# NeoPixel_6x4_Matrix.net
KiCad netlist of a schematic drawn in EAGLE
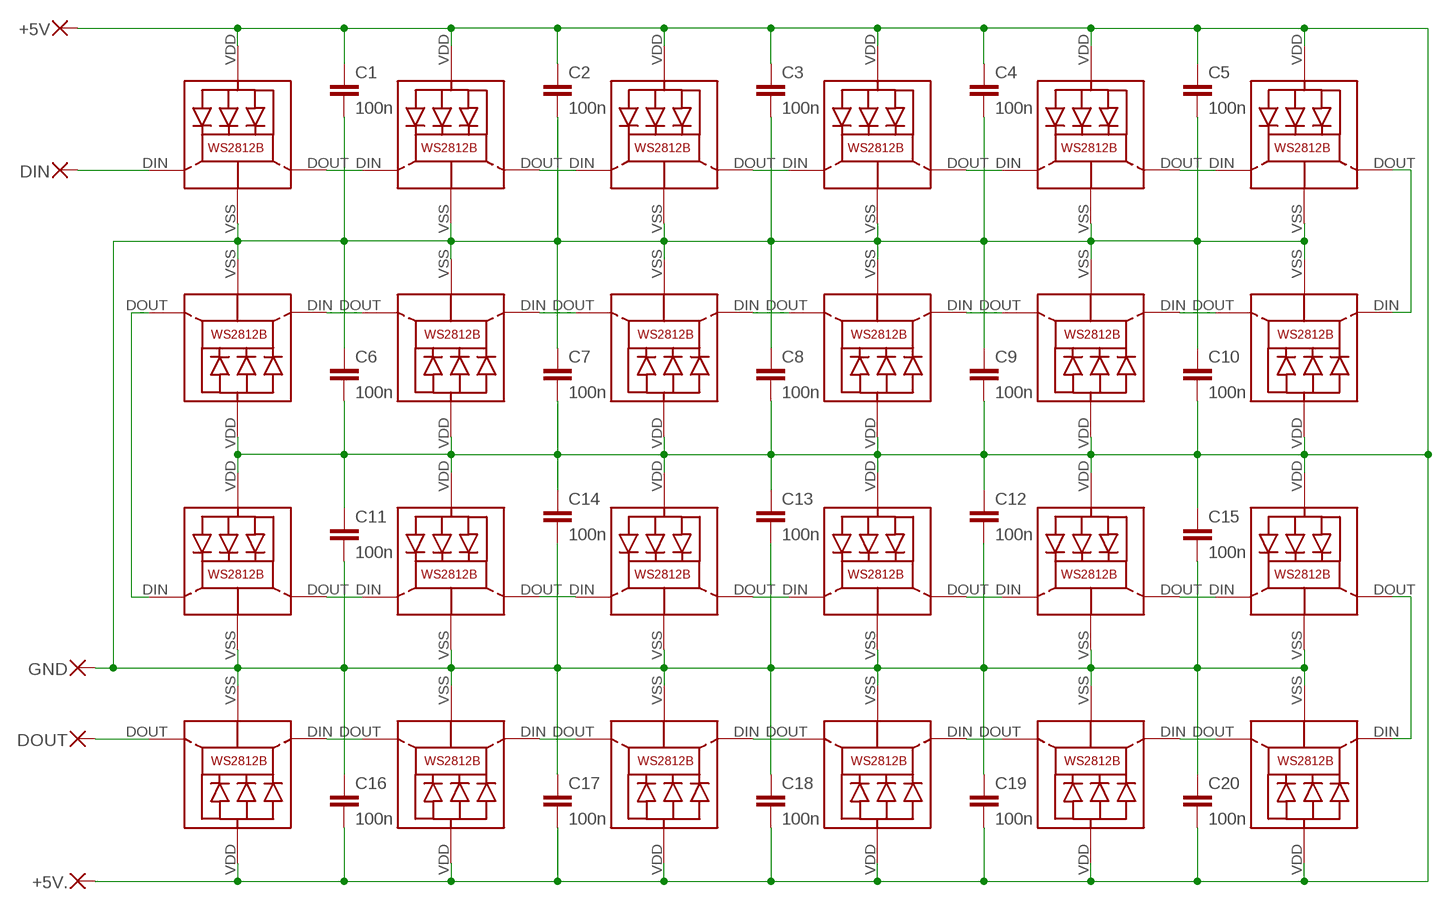
[diagram p0: schematic, sheet 1]

(export (version "E")
  (design (tool "Eeschema 10.0.6"))
  (components
    (comp (ref "+5V")
      (value "1,6/0,8")
      (footprint "eagle-import:1,6_0,8")
      (libsource (lib "eagle-import") (part "1,6/0,8"))
    )
    (comp (ref "+5V.")
      (value "1,6/0,8")
      (footprint "eagle-import:1,6_0,8")
      (libsource (lib "eagle-import") (part "1,6/0,8"))
    )
    (comp (ref "C1")
      (value "100n")
      (footprint "eagle-import:C0603")
      (libsource (lib "eagle-import") (part "C-EUC0603"))
    )
    (comp (ref "C2")
      (value "100n")
      (footprint "eagle-import:C0603")
      (libsource (lib "eagle-import") (part "C-EUC0603"))
    )
    (comp (ref "C3")
      (value "100n")
      (footprint "eagle-import:C0603")
      (libsource (lib "eagle-import") (part "C-EUC0603"))
    )
    (comp (ref "C4")
      (value "100n")
      (footprint "eagle-import:C0603")
      (libsource (lib "eagle-import") (part "C-EUC0603"))
    )
    (comp (ref "C5")
      (value "100n")
      (footprint "eagle-import:C0603")
      (libsource (lib "eagle-import") (part "C-EUC0603"))
    )
    (comp (ref "C6")
      (value "100n")
      (footprint "eagle-import:C0603")
      (libsource (lib "eagle-import") (part "C-EUC0603"))
    )
    (comp (ref "C7")
      (value "100n")
      (footprint "eagle-import:C0603")
      (libsource (lib "eagle-import") (part "C-EUC0603"))
    )
    (comp (ref "C8")
      (value "100n")
      (footprint "eagle-import:C0603")
      (libsource (lib "eagle-import") (part "C-EUC0603"))
    )
    (comp (ref "C9")
      (value "100n")
      (footprint "eagle-import:C0603")
      (libsource (lib "eagle-import") (part "C-EUC0603"))
    )
    (comp (ref "C10")
      (value "100n")
      (footprint "eagle-import:C0603")
      (libsource (lib "eagle-import") (part "C-EUC0603"))
    )
    (comp (ref "C11")
      (value "100n")
      (footprint "eagle-import:C0603")
      (libsource (lib "eagle-import") (part "C-EUC0603"))
    )
    (comp (ref "C12")
      (value "100n")
      (footprint "eagle-import:C0603")
      (libsource (lib "eagle-import") (part "C-EUC0603"))
    )
    (comp (ref "C13")
      (value "100n")
      (footprint "eagle-import:C0603")
      (libsource (lib "eagle-import") (part "C-EUC0603"))
    )
    (comp (ref "C14")
      (value "100n")
      (footprint "eagle-import:C0603")
      (libsource (lib "eagle-import") (part "C-EUC0603"))
    )
    (comp (ref "C15")
      (value "100n")
      (footprint "eagle-import:C0603")
      (libsource (lib "eagle-import") (part "C-EUC0603"))
    )
    (comp (ref "C16")
      (value "100n")
      (footprint "eagle-import:C0603")
      (libsource (lib "eagle-import") (part "C-EUC0603"))
    )
    (comp (ref "C17")
      (value "100n")
      (footprint "eagle-import:C0603")
      (libsource (lib "eagle-import") (part "C-EUC0603"))
    )
    (comp (ref "C18")
      (value "100n")
      (footprint "eagle-import:C0603")
      (libsource (lib "eagle-import") (part "C-EUC0603"))
    )
    (comp (ref "C19")
      (value "100n")
      (footprint "eagle-import:C0603")
      (libsource (lib "eagle-import") (part "C-EUC0603"))
    )
    (comp (ref "C20")
      (value "100n")
      (footprint "eagle-import:C0603")
      (libsource (lib "eagle-import") (part "C-EUC0603"))
    )
    (comp (ref "DIN")
      (value "1,6/0,8")
      (footprint "eagle-import:1,6_0,8")
      (libsource (lib "eagle-import") (part "1,6/0,8"))
    )
    (comp (ref "DOUT")
      (value "1,6/0,8")
      (footprint "eagle-import:1,6_0,8")
      (libsource (lib "eagle-import") (part "1,6/0,8"))
    )
    (comp (ref "GND")
      (value "1,6/0,8")
      (footprint "eagle-import:1,6_0,8")
      (libsource (lib "eagle-import") (part "1,6/0,8"))
    )
    (comp (ref "LED1")
      (value "WS2812B")
      (footprint "eagle-import:WS2812B")
      (libsource (lib "eagle-import") (part "WS2812B"))
    )
    (comp (ref "LED2")
      (value "WS2812B")
      (footprint "eagle-import:WS2812B")
      (libsource (lib "eagle-import") (part "WS2812B"))
    )
    (comp (ref "LED3")
      (value "WS2812B")
      (footprint "eagle-import:WS2812B")
      (libsource (lib "eagle-import") (part "WS2812B"))
    )
    (comp (ref "LED4")
      (value "WS2812B")
      (footprint "eagle-import:WS2812B")
      (libsource (lib "eagle-import") (part "WS2812B"))
    )
    (comp (ref "LED5")
      (value "WS2812B")
      (footprint "eagle-import:WS2812B")
      (libsource (lib "eagle-import") (part "WS2812B"))
    )
    (comp (ref "LED6")
      (value "WS2812B")
      (footprint "eagle-import:WS2812B")
      (libsource (lib "eagle-import") (part "WS2812B"))
    )
    (comp (ref "LED7")
      (value "WS2812B")
      (footprint "eagle-import:WS2812B")
      (libsource (lib "eagle-import") (part "WS2812B"))
    )
    (comp (ref "LED8")
      (value "WS2812B")
      (footprint "eagle-import:WS2812B")
      (libsource (lib "eagle-import") (part "WS2812B"))
    )
    (comp (ref "LED9")
      (value "WS2812B")
      (footprint "eagle-import:WS2812B")
      (libsource (lib "eagle-import") (part "WS2812B"))
    )
    (comp (ref "LED10")
      (value "WS2812B")
      (footprint "eagle-import:WS2812B")
      (libsource (lib "eagle-import") (part "WS2812B"))
    )
    (comp (ref "LED11")
      (value "WS2812B")
      (footprint "eagle-import:WS2812B")
      (libsource (lib "eagle-import") (part "WS2812B"))
    )
    (comp (ref "LED12")
      (value "WS2812B")
      (footprint "eagle-import:WS2812B")
      (libsource (lib "eagle-import") (part "WS2812B"))
    )
    (comp (ref "LED13")
      (value "WS2812B")
      (footprint "eagle-import:WS2812B")
      (libsource (lib "eagle-import") (part "WS2812B"))
    )
    (comp (ref "LED14")
      (value "WS2812B")
      (footprint "eagle-import:WS2812B")
      (libsource (lib "eagle-import") (part "WS2812B"))
    )
    (comp (ref "LED15")
      (value "WS2812B")
      (footprint "eagle-import:WS2812B")
      (libsource (lib "eagle-import") (part "WS2812B"))
    )
    (comp (ref "LED16")
      (value "WS2812B")
      (footprint "eagle-import:WS2812B")
      (libsource (lib "eagle-import") (part "WS2812B"))
    )
    (comp (ref "LED17")
      (value "WS2812B")
      (footprint "eagle-import:WS2812B")
      (libsource (lib "eagle-import") (part "WS2812B"))
    )
    (comp (ref "LED18")
      (value "WS2812B")
      (footprint "eagle-import:WS2812B")
      (libsource (lib "eagle-import") (part "WS2812B"))
    )
    (comp (ref "LED19")
      (value "WS2812B")
      (footprint "eagle-import:WS2812B")
      (libsource (lib "eagle-import") (part "WS2812B"))
    )
    (comp (ref "LED20")
      (value "WS2812B")
      (footprint "eagle-import:WS2812B")
      (libsource (lib "eagle-import") (part "WS2812B"))
    )
    (comp (ref "LED21")
      (value "WS2812B")
      (footprint "eagle-import:WS2812B")
      (libsource (lib "eagle-import") (part "WS2812B"))
    )
    (comp (ref "LED22")
      (value "WS2812B")
      (footprint "eagle-import:WS2812B")
      (libsource (lib "eagle-import") (part "WS2812B"))
    )
    (comp (ref "LED23")
      (value "WS2812B")
      (footprint "eagle-import:WS2812B")
      (libsource (lib "eagle-import") (part "WS2812B"))
    )
    (comp (ref "LED24")
      (value "WS2812B")
      (footprint "eagle-import:WS2812B")
      (libsource (lib "eagle-import") (part "WS2812B"))
    )
  )
  (nets
    (net (code "1") (name "Net-(+5V-P)") (class "Default")
      (node (ref "+5V") (pin "1") (pinfunction "P_1") (pintype "passive"))
      (node (ref "+5V.") (pin "1") (pinfunction "P_1") (pintype "passive"))
      (node (ref "C1") (pin "1") (pinfunction "1_1") (pintype "passive"))
      (node (ref "C10") (pin "2") (pinfunction "2_2") (pintype "passive"))
      (node (ref "C11") (pin "1") (pinfunction "1_1") (pintype "passive"))
      (node (ref "C12") (pin "1") (pinfunction "1_1") (pintype "passive"))
      (node (ref "C13") (pin "1") (pinfunction "1_1") (pintype "passive"))
      (node (ref "C14") (pin "1") (pinfunction "1_1") (pintype "passive"))
      (node (ref "C15") (pin "1") (pinfunction "1_1") (pintype "passive"))
      (node (ref "C16") (pin "2") (pinfunction "2_2") (pintype "passive"))
      (node (ref "C17") (pin "2") (pinfunction "2_2") (pintype "passive"))
      (node (ref "C18") (pin "2") (pinfunction "2_2") (pintype "passive"))
      (node (ref "C19") (pin "2") (pinfunction "2_2") (pintype "passive"))
      (node (ref "C2") (pin "1") (pinfunction "1_1") (pintype "passive"))
      (node (ref "C20") (pin "2") (pinfunction "2_2") (pintype "passive"))
      (node (ref "C3") (pin "1") (pinfunction "1_1") (pintype "passive"))
      (node (ref "C4") (pin "1") (pinfunction "1_1") (pintype "passive"))
      (node (ref "C5") (pin "1") (pinfunction "1_1") (pintype "passive"))
      (node (ref "C6") (pin "2") (pinfunction "2_2") (pintype "passive"))
      (node (ref "C7") (pin "2") (pinfunction "2_2") (pintype "passive"))
      (node (ref "C8") (pin "2") (pinfunction "2_2") (pintype "passive"))
      (node (ref "C9") (pin "2") (pinfunction "2_2") (pintype "passive"))
      (node (ref "LED1") (pin "VDD") (pinfunction "VDD_VDD") (pintype "power_in"))
      (node (ref "LED10") (pin "VDD") (pinfunction "VDD_VDD") (pintype "power_in"))
      (node (ref "LED11") (pin "VDD") (pinfunction "VDD_VDD") (pintype "power_in"))
      (node (ref "LED12") (pin "VDD") (pinfunction "VDD_VDD") (pintype "power_in"))
      (node (ref "LED13") (pin "VDD") (pinfunction "VDD_VDD") (pintype "power_in"))
      (node (ref "LED14") (pin "VDD") (pinfunction "VDD_VDD") (pintype "power_in"))
      (node (ref "LED15") (pin "VDD") (pinfunction "VDD_VDD") (pintype "power_in"))
      (node (ref "LED16") (pin "VDD") (pinfunction "VDD_VDD") (pintype "power_in"))
      (node (ref "LED17") (pin "VDD") (pinfunction "VDD_VDD") (pintype "power_in"))
      (node (ref "LED18") (pin "VDD") (pinfunction "VDD_VDD") (pintype "power_in"))
      (node (ref "LED19") (pin "VDD") (pinfunction "VDD_VDD") (pintype "power_in"))
      (node (ref "LED2") (pin "VDD") (pinfunction "VDD_VDD") (pintype "power_in"))
      (node (ref "LED20") (pin "VDD") (pinfunction "VDD_VDD") (pintype "power_in"))
      (node (ref "LED21") (pin "VDD") (pinfunction "VDD_VDD") (pintype "power_in"))
      (node (ref "LED22") (pin "VDD") (pinfunction "VDD_VDD") (pintype "power_in"))
      (node (ref "LED23") (pin "VDD") (pinfunction "VDD_VDD") (pintype "power_in"))
      (node (ref "LED24") (pin "VDD") (pinfunction "VDD_VDD") (pintype "power_in"))
      (node (ref "LED3") (pin "VDD") (pinfunction "VDD_VDD") (pintype "power_in"))
      (node (ref "LED4") (pin "VDD") (pinfunction "VDD_VDD") (pintype "power_in"))
      (node (ref "LED5") (pin "VDD") (pinfunction "VDD_VDD") (pintype "power_in"))
      (node (ref "LED6") (pin "VDD") (pinfunction "VDD_VDD") (pintype "power_in"))
      (node (ref "LED7") (pin "VDD") (pinfunction "VDD_VDD") (pintype "power_in"))
      (node (ref "LED8") (pin "VDD") (pinfunction "VDD_VDD") (pintype "power_in"))
      (node (ref "LED9") (pin "VDD") (pinfunction "VDD_VDD") (pintype "power_in"))
    )
    (net (code "2") (name "Net-(DIN-P)") (class "Default")
      (node (ref "DIN") (pin "1") (pinfunction "P_1") (pintype "passive"))
      (node (ref "LED1") (pin "DIN") (pinfunction "DI_DIN") (pintype "input"))
    )
    (net (code "3") (name "Net-(DOUT-P)") (class "Default")
      (node (ref "DOUT") (pin "1") (pinfunction "P_1") (pintype "passive"))
      (node (ref "LED24") (pin "DOUT") (pinfunction "DO_DOUT") (pintype "output"))
    )
    (net (code "4") (name "Net-(GND-P)") (class "Default")
      (node (ref "C1") (pin "2") (pinfunction "2_2") (pintype "passive"))
      (node (ref "C10") (pin "1") (pinfunction "1_1") (pintype "passive"))
      (node (ref "C11") (pin "2") (pinfunction "2_2") (pintype "passive"))
      (node (ref "C12") (pin "2") (pinfunction "2_2") (pintype "passive"))
      (node (ref "C13") (pin "2") (pinfunction "2_2") (pintype "passive"))
      (node (ref "C14") (pin "2") (pinfunction "2_2") (pintype "passive"))
      (node (ref "C15") (pin "2") (pinfunction "2_2") (pintype "passive"))
      (node (ref "C16") (pin "1") (pinfunction "1_1") (pintype "passive"))
      (node (ref "C17") (pin "1") (pinfunction "1_1") (pintype "passive"))
      (node (ref "C18") (pin "1") (pinfunction "1_1") (pintype "passive"))
      (node (ref "C19") (pin "1") (pinfunction "1_1") (pintype "passive"))
      (node (ref "C2") (pin "2") (pinfunction "2_2") (pintype "passive"))
      (node (ref "C20") (pin "1") (pinfunction "1_1") (pintype "passive"))
      (node (ref "C3") (pin "2") (pinfunction "2_2") (pintype "passive"))
      (node (ref "C4") (pin "2") (pinfunction "2_2") (pintype "passive"))
      (node (ref "C5") (pin "2") (pinfunction "2_2") (pintype "passive"))
      (node (ref "C6") (pin "1") (pinfunction "1_1") (pintype "passive"))
      (node (ref "C7") (pin "1") (pinfunction "1_1") (pintype "passive"))
      (node (ref "C8") (pin "1") (pinfunction "1_1") (pintype "passive"))
      (node (ref "C9") (pin "1") (pinfunction "1_1") (pintype "passive"))
      (node (ref "GND") (pin "1") (pinfunction "P_1") (pintype "passive"))
      (node (ref "LED1") (pin "VSS") (pinfunction "GND_VSS") (pintype "power_in"))
      (node (ref "LED10") (pin "VSS") (pinfunction "GND_VSS") (pintype "power_in"))
      (node (ref "LED11") (pin "VSS") (pinfunction "GND_VSS") (pintype "power_in"))
      (node (ref "LED12") (pin "VSS") (pinfunction "GND_VSS") (pintype "power_in"))
      (node (ref "LED13") (pin "VSS") (pinfunction "GND_VSS") (pintype "power_in"))
      (node (ref "LED14") (pin "VSS") (pinfunction "GND_VSS") (pintype "power_in"))
      (node (ref "LED15") (pin "VSS") (pinfunction "GND_VSS") (pintype "power_in"))
      (node (ref "LED16") (pin "VSS") (pinfunction "GND_VSS") (pintype "power_in"))
      (node (ref "LED17") (pin "VSS") (pinfunction "GND_VSS") (pintype "power_in"))
      (node (ref "LED18") (pin "VSS") (pinfunction "GND_VSS") (pintype "power_in"))
      (node (ref "LED19") (pin "VSS") (pinfunction "GND_VSS") (pintype "power_in"))
      (node (ref "LED2") (pin "VSS") (pinfunction "GND_VSS") (pintype "power_in"))
      (node (ref "LED20") (pin "VSS") (pinfunction "GND_VSS") (pintype "power_in"))
      (node (ref "LED21") (pin "VSS") (pinfunction "GND_VSS") (pintype "power_in"))
      (node (ref "LED22") (pin "VSS") (pinfunction "GND_VSS") (pintype "power_in"))
      (node (ref "LED23") (pin "VSS") (pinfunction "GND_VSS") (pintype "power_in"))
      (node (ref "LED24") (pin "VSS") (pinfunction "GND_VSS") (pintype "power_in"))
      (node (ref "LED3") (pin "VSS") (pinfunction "GND_VSS") (pintype "power_in"))
      (node (ref "LED4") (pin "VSS") (pinfunction "GND_VSS") (pintype "power_in"))
      (node (ref "LED5") (pin "VSS") (pinfunction "GND_VSS") (pintype "power_in"))
      (node (ref "LED6") (pin "VSS") (pinfunction "GND_VSS") (pintype "power_in"))
      (node (ref "LED7") (pin "VSS") (pinfunction "GND_VSS") (pintype "power_in"))
      (node (ref "LED8") (pin "VSS") (pinfunction "GND_VSS") (pintype "power_in"))
      (node (ref "LED9") (pin "VSS") (pinfunction "GND_VSS") (pintype "power_in"))
    )
    (net (code "5") (name "Net-(LED1-DO)") (class "Default")
      (node (ref "LED1") (pin "DOUT") (pinfunction "DO_DOUT") (pintype "output"))
      (node (ref "LED2") (pin "DIN") (pinfunction "DI_DIN") (pintype "input"))
    )
    (net (code "6") (name "Net-(LED2-DO)") (class "Default")
      (node (ref "LED2") (pin "DOUT") (pinfunction "DO_DOUT") (pintype "output"))
      (node (ref "LED3") (pin "DIN") (pinfunction "DI_DIN") (pintype "input"))
    )
    (net (code "7") (name "Net-(LED3-DO)") (class "Default")
      (node (ref "LED3") (pin "DOUT") (pinfunction "DO_DOUT") (pintype "output"))
      (node (ref "LED4") (pin "DIN") (pinfunction "DI_DIN") (pintype "input"))
    )
    (net (code "8") (name "Net-(LED4-DO)") (class "Default")
      (node (ref "LED4") (pin "DOUT") (pinfunction "DO_DOUT") (pintype "output"))
      (node (ref "LED5") (pin "DIN") (pinfunction "DI_DIN") (pintype "input"))
    )
    (net (code "9") (name "Net-(LED5-DO)") (class "Default")
      (node (ref "LED5") (pin "DOUT") (pinfunction "DO_DOUT") (pintype "output"))
      (node (ref "LED6") (pin "DIN") (pinfunction "DI_DIN") (pintype "input"))
    )
    (net (code "10") (name "Net-(LED6-DO)") (class "Default")
      (node (ref "LED6") (pin "DOUT") (pinfunction "DO_DOUT") (pintype "output"))
      (node (ref "LED7") (pin "DIN") (pinfunction "DI_DIN") (pintype "input"))
    )
    (net (code "11") (name "Net-(LED7-DO)") (class "Default")
      (node (ref "LED7") (pin "DOUT") (pinfunction "DO_DOUT") (pintype "output"))
      (node (ref "LED8") (pin "DIN") (pinfunction "DI_DIN") (pintype "input"))
    )
    (net (code "12") (name "Net-(LED8-DO)") (class "Default")
      (node (ref "LED8") (pin "DOUT") (pinfunction "DO_DOUT") (pintype "output"))
      (node (ref "LED9") (pin "DIN") (pinfunction "DI_DIN") (pintype "input"))
    )
    (net (code "13") (name "Net-(LED10-DI)") (class "Default")
      (node (ref "LED10") (pin "DIN") (pinfunction "DI_DIN") (pintype "input"))
      (node (ref "LED9") (pin "DOUT") (pinfunction "DO_DOUT") (pintype "output"))
    )
    (net (code "14") (name "Net-(LED10-DO)") (class "Default")
      (node (ref "LED10") (pin "DOUT") (pinfunction "DO_DOUT") (pintype "output"))
      (node (ref "LED11") (pin "DIN") (pinfunction "DI_DIN") (pintype "input"))
    )
    (net (code "15") (name "Net-(LED11-DO)") (class "Default")
      (node (ref "LED11") (pin "DOUT") (pinfunction "DO_DOUT") (pintype "output"))
      (node (ref "LED12") (pin "DIN") (pinfunction "DI_DIN") (pintype "input"))
    )
    (net (code "16") (name "Net-(LED12-DO)") (class "Default")
      (node (ref "LED12") (pin "DOUT") (pinfunction "DO_DOUT") (pintype "output"))
      (node (ref "LED13") (pin "DIN") (pinfunction "DI_DIN") (pintype "input"))
    )
    (net (code "17") (name "Net-(LED13-DO)") (class "Default")
      (node (ref "LED13") (pin "DOUT") (pinfunction "DO_DOUT") (pintype "output"))
      (node (ref "LED14") (pin "DIN") (pinfunction "DI_DIN") (pintype "input"))
    )
    (net (code "18") (name "Net-(LED14-DO)") (class "Default")
      (node (ref "LED14") (pin "DOUT") (pinfunction "DO_DOUT") (pintype "output"))
      (node (ref "LED15") (pin "DIN") (pinfunction "DI_DIN") (pintype "input"))
    )
    (net (code "19") (name "Net-(LED15-DO)") (class "Default")
      (node (ref "LED15") (pin "DOUT") (pinfunction "DO_DOUT") (pintype "output"))
      (node (ref "LED16") (pin "DIN") (pinfunction "DI_DIN") (pintype "input"))
    )
    (net (code "20") (name "Net-(LED16-DO)") (class "Default")
      (node (ref "LED16") (pin "DOUT") (pinfunction "DO_DOUT") (pintype "output"))
      (node (ref "LED17") (pin "DIN") (pinfunction "DI_DIN") (pintype "input"))
    )
    (net (code "21") (name "Net-(LED17-DO)") (class "Default")
      (node (ref "LED17") (pin "DOUT") (pinfunction "DO_DOUT") (pintype "output"))
      (node (ref "LED18") (pin "DIN") (pinfunction "DI_DIN") (pintype "input"))
    )
    (net (code "22") (name "Net-(LED18-DO)") (class "Default")
      (node (ref "LED18") (pin "DOUT") (pinfunction "DO_DOUT") (pintype "output"))
      (node (ref "LED19") (pin "DIN") (pinfunction "DI_DIN") (pintype "input"))
    )
    (net (code "23") (name "Net-(LED19-DO)") (class "Default")
      (node (ref "LED19") (pin "DOUT") (pinfunction "DO_DOUT") (pintype "output"))
      (node (ref "LED20") (pin "DIN") (pinfunction "DI_DIN") (pintype "input"))
    )
    (net (code "24") (name "Net-(LED20-DO)") (class "Default")
      (node (ref "LED20") (pin "DOUT") (pinfunction "DO_DOUT") (pintype "output"))
      (node (ref "LED21") (pin "DIN") (pinfunction "DI_DIN") (pintype "input"))
    )
    (net (code "25") (name "Net-(LED21-DO)") (class "Default")
      (node (ref "LED21") (pin "DOUT") (pinfunction "DO_DOUT") (pintype "output"))
      (node (ref "LED22") (pin "DIN") (pinfunction "DI_DIN") (pintype "input"))
    )
    (net (code "26") (name "Net-(LED22-DO)") (class "Default")
      (node (ref "LED22") (pin "DOUT") (pinfunction "DO_DOUT") (pintype "output"))
      (node (ref "LED23") (pin "DIN") (pinfunction "DI_DIN") (pintype "input"))
    )
    (net (code "27") (name "Net-(LED23-DO)") (class "Default")
      (node (ref "LED23") (pin "DOUT") (pinfunction "DO_DOUT") (pintype "output"))
      (node (ref "LED24") (pin "DIN") (pinfunction "DI_DIN") (pintype "input"))
    )
  )
)
